# FT757GX_light_bar_RH.net
KiCad netlist of a schematic drawn in EasyEDA
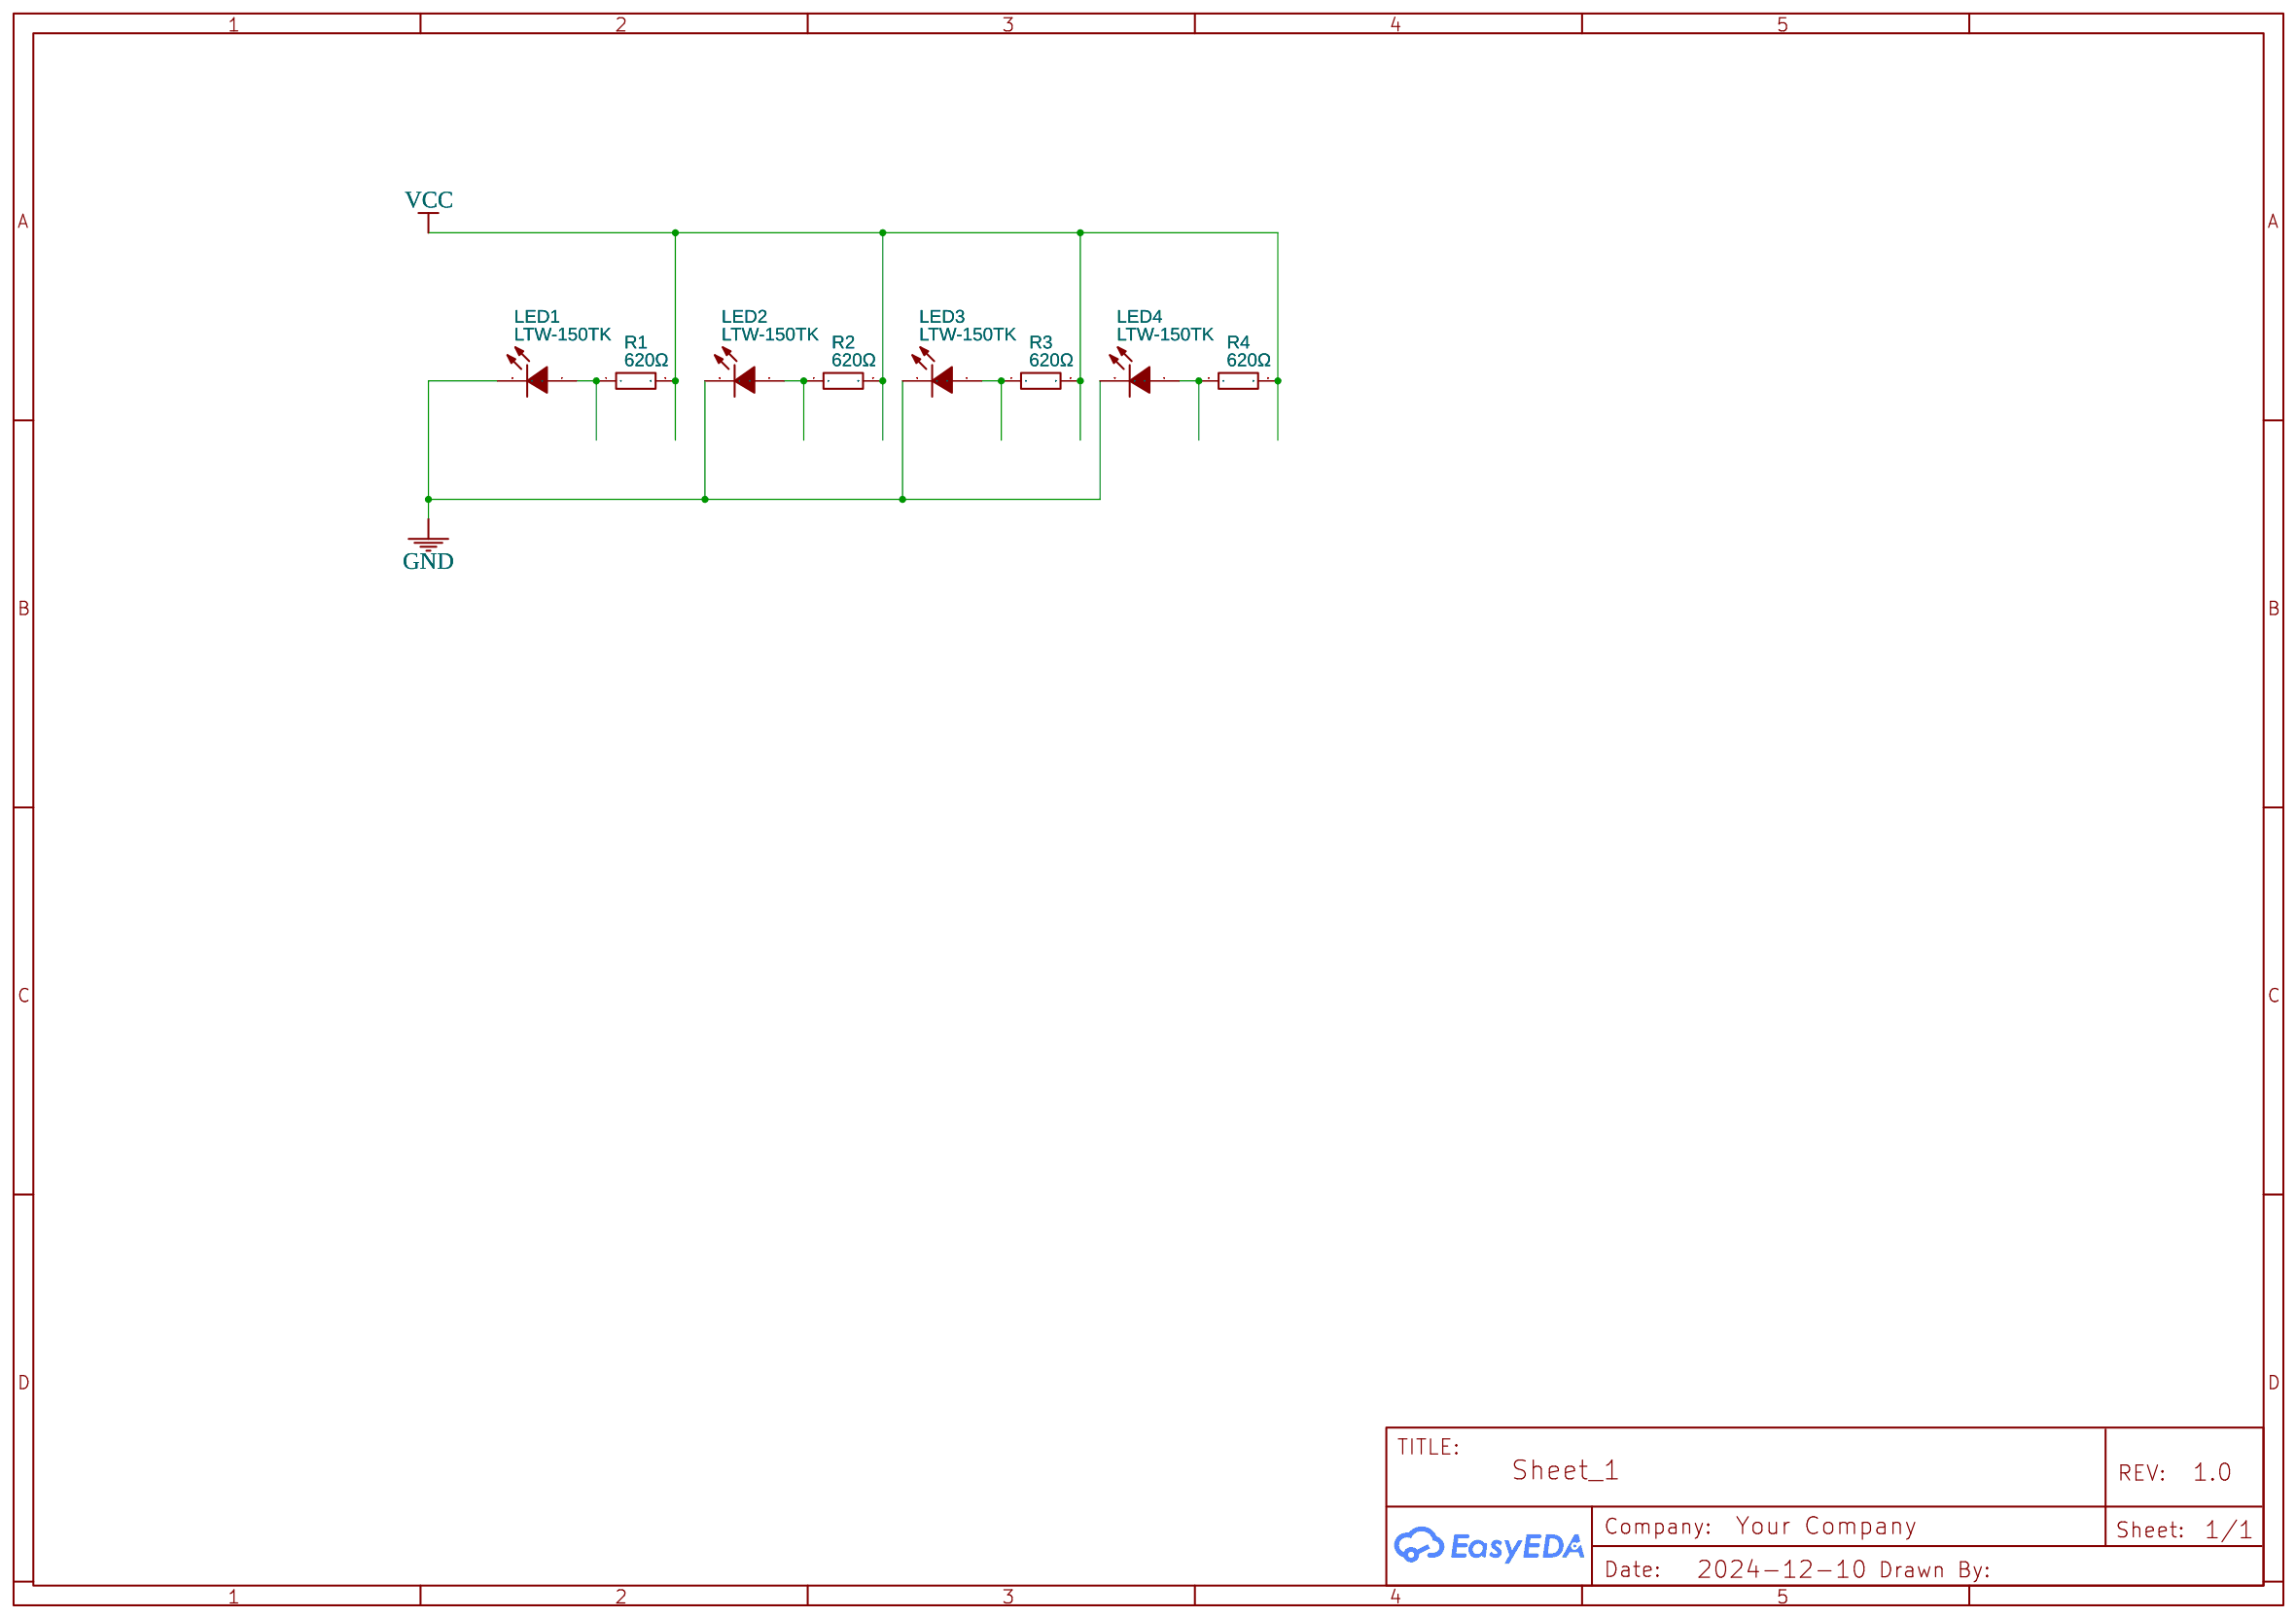
[diagram p0: schematic sheet]

(export (version "E")
  (design (tool "Eeschema 10.0.6"))
  (components
    (comp (ref "LED1")
      (value "LTW-150TK")
      (fields (field (name "Manufacturer") "LITEON(光宝)"))
      (libsource (lib "") (part "LTW-150TK"))
    )
    (comp (ref "LED2")
      (value "LTW-150TK")
      (fields (field (name "Manufacturer") "LITEON(光宝)"))
      (libsource (lib "") (part "LTW-150TK"))
    )
    (comp (ref "LED3")
      (value "LTW-150TK")
      (fields (field (name "Manufacturer") "LITEON(光宝)"))
      (libsource (lib "") (part "LTW-150TK"))
    )
    (comp (ref "LED4")
      (value "LTW-150TK")
      (fields (field (name "Manufacturer") "LITEON(光宝)"))
      (libsource (lib "") (part "LTW-150TK"))
    )
    (comp (ref "R1")
      (value "620Ω")
      (fields (field (name "Manufacturer Part") "AECR1206F620RK9") (field (name "Manufacturer") "RESI(开步睿思)"))
      (libsource (lib "") (part "AECR1206F620RK9"))
    )
    (comp (ref "R2")
      (value "620Ω")
      (fields (field (name "Manufacturer Part") "AECR1206F620RK9") (field (name "Manufacturer") "RESI(开步睿思)"))
      (libsource (lib "") (part "AECR1206F620RK9"))
    )
    (comp (ref "R3")
      (value "620Ω")
      (fields (field (name "Manufacturer Part") "AECR1206F620RK9") (field (name "Manufacturer") "RESI(开步睿思)"))
      (libsource (lib "") (part "AECR1206F620RK9"))
    )
    (comp (ref "R4")
      (value "620Ω")
      (fields (field (name "Manufacturer Part") "AECR1206F620RK9") (field (name "Manufacturer") "RESI(开步睿思)"))
      (libsource (lib "") (part "AECR1206F620RK9"))
    )
  )
  (nets
    (net (code "1") (name "GND") (class "Default")
      (node (ref "LED1") (pin "2") (pinfunction "K_2") (pintype "unspecified"))
      (node (ref "LED2") (pin "2") (pinfunction "K_2") (pintype "unspecified"))
      (node (ref "LED3") (pin "2") (pinfunction "K_2") (pintype "unspecified"))
      (node (ref "LED4") (pin "2") (pinfunction "K_2") (pintype "unspecified"))
    )
    (net (code "2") (name "Net-(LED1-A)") (class "Default")
      (node (ref "LED1") (pin "1") (pinfunction "A_1") (pintype "unspecified"))
      (node (ref "R1") (pin "1") (pinfunction "1_1") (pintype "unspecified"))
    )
    (net (code "3") (name "Net-(LED2-A)") (class "Default")
      (node (ref "LED2") (pin "1") (pinfunction "A_1") (pintype "unspecified"))
      (node (ref "R2") (pin "1") (pinfunction "1_1") (pintype "unspecified"))
    )
    (net (code "4") (name "Net-(LED3-A)") (class "Default")
      (node (ref "LED3") (pin "1") (pinfunction "A_1") (pintype "unspecified"))
      (node (ref "R3") (pin "1") (pinfunction "1_1") (pintype "unspecified"))
    )
    (net (code "5") (name "Net-(LED4-A)") (class "Default")
      (node (ref "LED4") (pin "1") (pinfunction "A_1") (pintype "unspecified"))
      (node (ref "R4") (pin "1") (pinfunction "1_1") (pintype "unspecified"))
    )
    (net (code "6") (name "VCC") (class "Default")
      (node (ref "R1") (pin "2") (pinfunction "2_2") (pintype "unspecified"))
      (node (ref "R2") (pin "2") (pinfunction "2_2") (pintype "unspecified"))
      (node (ref "R3") (pin "2") (pinfunction "2_2") (pintype "unspecified"))
      (node (ref "R4") (pin "2") (pinfunction "2_2") (pintype "unspecified"))
    )
  )
)
